# sensor.net
KiCad netlist of a schematic drawn in EAGLE
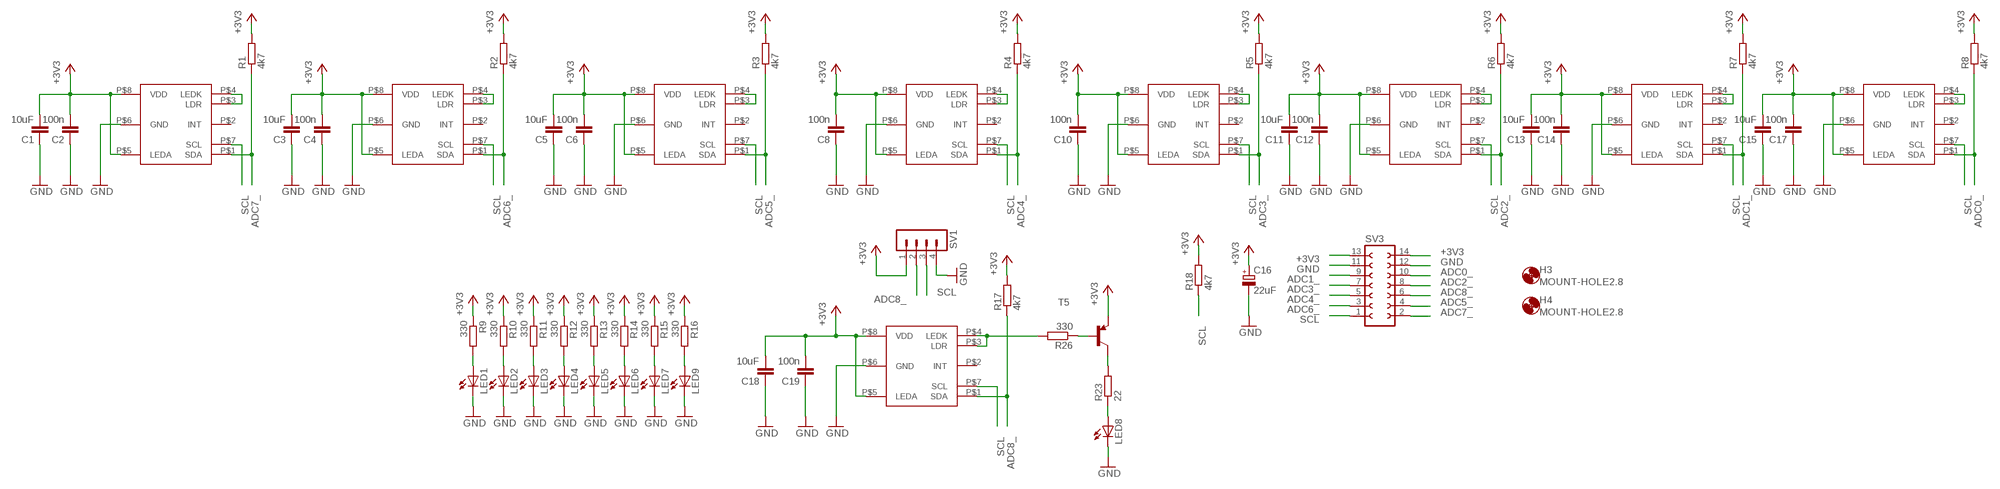
[diagram p0: schematic, sheet 1]

(export (version "E")
  (design (tool "Eeschema 10.0.6"))
  (components
    (comp (ref "C1")
      (value "10uF")
      (footprint "eagle-import:C0805")
      (libsource (lib "eagle-import") (part "C-EUC0805"))
    )
    (comp (ref "C2")
      (value "100n")
      (footprint "eagle-import:C0805")
      (libsource (lib "eagle-import") (part "C-EUC0805"))
    )
    (comp (ref "C3")
      (value "10uF")
      (footprint "eagle-import:C0805")
      (libsource (lib "eagle-import") (part "C-EUC0805"))
    )
    (comp (ref "C4")
      (value "100n")
      (footprint "eagle-import:C0805")
      (libsource (lib "eagle-import") (part "C-EUC0805"))
    )
    (comp (ref "C5")
      (value "10uF")
      (footprint "eagle-import:C0805")
      (libsource (lib "eagle-import") (part "C-EUC0805"))
    )
    (comp (ref "C6")
      (value "100n")
      (footprint "eagle-import:C0805")
      (libsource (lib "eagle-import") (part "C-EUC0805"))
    )
    (comp (ref "C8")
      (value "100n")
      (footprint "eagle-import:C0805")
      (libsource (lib "eagle-import") (part "C-EUC0805"))
    )
    (comp (ref "C10")
      (value "100n")
      (footprint "eagle-import:C0805")
      (libsource (lib "eagle-import") (part "C-EUC0805"))
    )
    (comp (ref "C11")
      (value "10uF")
      (footprint "eagle-import:C0805")
      (libsource (lib "eagle-import") (part "C-EUC0805"))
    )
    (comp (ref "C12")
      (value "100n")
      (footprint "eagle-import:C0805")
      (libsource (lib "eagle-import") (part "C-EUC0805"))
    )
    (comp (ref "C13")
      (value "10uF")
      (footprint "eagle-import:C0805")
      (libsource (lib "eagle-import") (part "C-EUC0805"))
    )
    (comp (ref "C14")
      (value "100n")
      (footprint "eagle-import:C0805")
      (libsource (lib "eagle-import") (part "C-EUC0805"))
    )
    (comp (ref "C15")
      (value "10uF")
      (footprint "eagle-import:C0805")
      (libsource (lib "eagle-import") (part "C-EUC0805"))
    )
    (comp (ref "C16")
      (value "22uF")
      (footprint "eagle-import:153CLV-0505")
      (libsource (lib "eagle-import") (part "CPOL-EU153CLV-0505"))
    )
    (comp (ref "C17")
      (value "100n")
      (footprint "eagle-import:C0805")
      (libsource (lib "eagle-import") (part "C-EUC0805"))
    )
    (comp (ref "C18")
      (value "10uF")
      (footprint "eagle-import:C0805")
      (libsource (lib "eagle-import") (part "C-EUC0805"))
    )
    (comp (ref "C19")
      (value "100n")
      (footprint "eagle-import:C0805")
      (libsource (lib "eagle-import") (part "C-EUC0805"))
    )
    (comp (ref "H3")
      (value "MOUNT-HOLE2.8")
      (footprint "eagle-import:2,8")
      (libsource (lib "eagle-import") (part "MOUNT-HOLE2.8"))
    )
    (comp (ref "H4")
      (value "MOUNT-HOLE2.8")
      (footprint "eagle-import:2,8")
      (libsource (lib "eagle-import") (part "MOUNT-HOLE2.8"))
    )
    (comp (ref "LED1")
      (value "LEDCHIPLED_1206")
      (footprint "eagle-import:CHIPLED_1206")
      (libsource (lib "eagle-import") (part "my_parts_LEDCHIPLED_1206"))
    )
    (comp (ref "LED2")
      (value "LEDCHIPLED_1206")
      (footprint "eagle-import:CHIPLED_1206")
      (libsource (lib "eagle-import") (part "my_parts_LEDCHIPLED_1206"))
    )
    (comp (ref "LED3")
      (value "LEDCHIPLED_1206")
      (footprint "eagle-import:CHIPLED_1206")
      (libsource (lib "eagle-import") (part "my_parts_LEDCHIPLED_1206"))
    )
    (comp (ref "LED4")
      (value "LEDCHIPLED_1206")
      (footprint "eagle-import:CHIPLED_1206")
      (libsource (lib "eagle-import") (part "my_parts_LEDCHIPLED_1206"))
    )
    (comp (ref "LED5")
      (value "LEDCHIPLED_1206")
      (footprint "eagle-import:CHIPLED_1206")
      (libsource (lib "eagle-import") (part "my_parts_LEDCHIPLED_1206"))
    )
    (comp (ref "LED6")
      (value "LEDCHIPLED_1206")
      (footprint "eagle-import:CHIPLED_1206")
      (libsource (lib "eagle-import") (part "my_parts_LEDCHIPLED_1206"))
    )
    (comp (ref "LED7")
      (value "LEDCHIPLED_1206")
      (footprint "eagle-import:CHIPLED_1206")
      (libsource (lib "eagle-import") (part "my_parts_LEDCHIPLED_1206"))
    )
    (comp (ref "LED8")
      (value "LED5MM")
      (footprint "eagle-import:LED5MM")
      (libsource (lib "eagle-import") (part "LED5MM"))
    )
    (comp (ref "LED9")
      (value "LEDCHIPLED_1206")
      (footprint "eagle-import:CHIPLED_1206")
      (libsource (lib "eagle-import") (part "my_parts_LEDCHIPLED_1206"))
    )
    (comp (ref "R1")
      (value "4k7")
      (footprint "eagle-import:M0805")
      (libsource (lib "eagle-import") (part "R-EU_M0805"))
    )
    (comp (ref "R2")
      (value "4k7")
      (footprint "eagle-import:M0805")
      (libsource (lib "eagle-import") (part "R-EU_M0805"))
    )
    (comp (ref "R3")
      (value "4k7")
      (footprint "eagle-import:M0805")
      (libsource (lib "eagle-import") (part "R-EU_M0805"))
    )
    (comp (ref "R4")
      (value "4k7")
      (footprint "eagle-import:M0805")
      (libsource (lib "eagle-import") (part "R-EU_M0805"))
    )
    (comp (ref "R5")
      (value "4k7")
      (footprint "eagle-import:M0805")
      (libsource (lib "eagle-import") (part "R-EU_M0805"))
    )
    (comp (ref "R6")
      (value "4k7")
      (footprint "eagle-import:M0805")
      (libsource (lib "eagle-import") (part "R-EU_M0805"))
    )
    (comp (ref "R7")
      (value "4k7")
      (footprint "eagle-import:M0805")
      (libsource (lib "eagle-import") (part "R-EU_M0805"))
    )
    (comp (ref "R8")
      (value "4k7")
      (footprint "eagle-import:M0805")
      (libsource (lib "eagle-import") (part "R-EU_M0805"))
    )
    (comp (ref "R9")
      (value "330")
      (footprint "eagle-import:M0805")
      (libsource (lib "eagle-import") (part "R-EU_M0805"))
    )
    (comp (ref "R10")
      (value "330")
      (footprint "eagle-import:M0805")
      (libsource (lib "eagle-import") (part "R-EU_M0805"))
    )
    (comp (ref "R11")
      (value "330")
      (footprint "eagle-import:M0805")
      (libsource (lib "eagle-import") (part "R-EU_M0805"))
    )
    (comp (ref "R12")
      (value "330")
      (footprint "eagle-import:M0805")
      (libsource (lib "eagle-import") (part "R-EU_M0805"))
    )
    (comp (ref "R13")
      (value "330")
      (footprint "eagle-import:M0805")
      (libsource (lib "eagle-import") (part "R-EU_M0805"))
    )
    (comp (ref "R14")
      (value "330")
      (footprint "eagle-import:M0805")
      (libsource (lib "eagle-import") (part "R-EU_M0805"))
    )
    (comp (ref "R15")
      (value "330")
      (footprint "eagle-import:M0805")
      (libsource (lib "eagle-import") (part "R-EU_M0805"))
    )
    (comp (ref "R16")
      (value "330")
      (footprint "eagle-import:M0805")
      (libsource (lib "eagle-import") (part "R-EU_M0805"))
    )
    (comp (ref "R17")
      (value "4k7")
      (footprint "eagle-import:M0805")
      (libsource (lib "eagle-import") (part "R-EU_M0805"))
    )
    (comp (ref "R18")
      (value "4k7")
      (footprint "eagle-import:M0805")
      (libsource (lib "eagle-import") (part "R-EU_M0805"))
    )
    (comp (ref "R23")
      (value "22")
      (footprint "eagle-import:M0805")
      (libsource (lib "eagle-import") (part "R-EU_M0805"))
    )
    (comp (ref "R26")
      (value "330")
      (footprint "eagle-import:M0805")
      (libsource (lib "eagle-import") (part "R-EU_M0805"))
    )
    (comp (ref "SV1")
      (value "MA04-1")
      (footprint "eagle-import:MA04-1")
      (libsource (lib "eagle-import") (part "MA04-1"))
    )
    (comp (ref "SV3")
      (value "FE07-2")
      (footprint "eagle-import:FE07-2")
      (libsource (lib "eagle-import") (part "FE07-2"))
    )
    (comp (ref "T5")
      (value "BC857A-PNP-SOT23-BEC")
      (footprint "eagle-import:SOT23-BEC")
      (libsource (lib "eagle-import") (part "-PNP-SOT23-BECBC857A"))
    )
    (comp (ref "U$1")
      (value "APDS9950")
      (footprint "eagle-import:APDS9950")
      (libsource (lib "eagle-import") (part "APDS9950"))
    )
    (comp (ref "U$2")
      (value "APDS9950_EDGE")
      (footprint "eagle-import:APDS9950_EDGE")
      (libsource (lib "eagle-import") (part "APDS9950_EDGE"))
    )
    (comp (ref "U$4")
      (value "APDS9950")
      (footprint "eagle-import:APDS9950")
      (libsource (lib "eagle-import") (part "APDS9950"))
    )
    (comp (ref "U$5")
      (value "APDS9950")
      (footprint "eagle-import:APDS9950")
      (libsource (lib "eagle-import") (part "APDS9950"))
    )
    (comp (ref "U$6")
      (value "APDS9950")
      (footprint "eagle-import:APDS9950")
      (libsource (lib "eagle-import") (part "APDS9950"))
    )
    (comp (ref "U$7")
      (value "APDS9950")
      (footprint "eagle-import:APDS9950")
      (libsource (lib "eagle-import") (part "APDS9950"))
    )
    (comp (ref "U$8")
      (value "APDS9950")
      (footprint "eagle-import:APDS9950")
      (libsource (lib "eagle-import") (part "APDS9950"))
    )
    (comp (ref "U$9")
      (value "APDS9950")
      (footprint "eagle-import:APDS9950")
      (libsource (lib "eagle-import") (part "APDS9950"))
    )
    (comp (ref "U$10")
      (value "APDS9950")
      (footprint "eagle-import:APDS9950")
      (libsource (lib "eagle-import") (part "APDS9950"))
    )
  )
  (nets
    (net (code "1") (name "+3V3") (class "Default")
      (node (ref "C1") (pin "2") (pinfunction "2_2") (pintype "passive"))
      (node (ref "C10") (pin "2") (pinfunction "2_2") (pintype "passive"))
      (node (ref "C11") (pin "2") (pinfunction "2_2") (pintype "passive"))
      (node (ref "C12") (pin "2") (pinfunction "2_2") (pintype "passive"))
      (node (ref "C13") (pin "2") (pinfunction "2_2") (pintype "passive"))
      (node (ref "C14") (pin "2") (pinfunction "2_2") (pintype "passive"))
      (node (ref "C15") (pin "2") (pinfunction "2_2") (pintype "passive"))
      (node (ref "C16") (pin "+") (pinfunction "+_+") (pintype "passive"))
      (node (ref "C17") (pin "2") (pinfunction "2_2") (pintype "passive"))
      (node (ref "C18") (pin "2") (pinfunction "2_2") (pintype "passive"))
      (node (ref "C19") (pin "2") (pinfunction "2_2") (pintype "passive"))
      (node (ref "C2") (pin "2") (pinfunction "2_2") (pintype "passive"))
      (node (ref "C3") (pin "2") (pinfunction "2_2") (pintype "passive"))
      (node (ref "C4") (pin "2") (pinfunction "2_2") (pintype "passive"))
      (node (ref "C5") (pin "2") (pinfunction "2_2") (pintype "passive"))
      (node (ref "C6") (pin "2") (pinfunction "2_2") (pintype "passive"))
      (node (ref "C8") (pin "2") (pinfunction "2_2") (pintype "passive"))
      (node (ref "R1") (pin "2") (pinfunction "2_2") (pintype "passive"))
      (node (ref "R10") (pin "1") (pinfunction "1_1") (pintype "passive"))
      (node (ref "R11") (pin "1") (pinfunction "1_1") (pintype "passive"))
      (node (ref "R12") (pin "1") (pinfunction "1_1") (pintype "passive"))
      (node (ref "R13") (pin "1") (pinfunction "1_1") (pintype "passive"))
      (node (ref "R14") (pin "1") (pinfunction "1_1") (pintype "passive"))
      (node (ref "R15") (pin "1") (pinfunction "1_1") (pintype "passive"))
      (node (ref "R16") (pin "1") (pinfunction "1_1") (pintype "passive"))
      (node (ref "R17") (pin "2") (pinfunction "2_2") (pintype "passive"))
      (node (ref "R18") (pin "2") (pinfunction "2_2") (pintype "passive"))
      (node (ref "R2") (pin "2") (pinfunction "2_2") (pintype "passive"))
      (node (ref "R3") (pin "2") (pinfunction "2_2") (pintype "passive"))
      (node (ref "R4") (pin "2") (pinfunction "2_2") (pintype "passive"))
      (node (ref "R5") (pin "2") (pinfunction "2_2") (pintype "passive"))
      (node (ref "R6") (pin "2") (pinfunction "2_2") (pintype "passive"))
      (node (ref "R7") (pin "2") (pinfunction "2_2") (pintype "passive"))
      (node (ref "R8") (pin "2") (pinfunction "2_2") (pintype "passive"))
      (node (ref "R9") (pin "1") (pinfunction "1_1") (pintype "passive"))
      (node (ref "SV1") (pin "1") (pinfunction "1_1") (pintype "passive"))
      (node (ref "SV3") (pin "13") (pinfunction "13_13") (pintype "passive"))
      (node (ref "SV3") (pin "14") (pinfunction "14_14") (pintype "passive"))
      (node (ref "T5") (pin "E") (pinfunction "E_E") (pintype "passive"))
      (node (ref "U$1") (pin "P$5") (pinfunction "LEDA_P$5") (pintype "bidirectional"))
      (node (ref "U$1") (pin "P$8") (pinfunction "VDD_P$8") (pintype "bidirectional"))
      (node (ref "U$10") (pin "P$5") (pinfunction "LEDA_P$5") (pintype "bidirectional"))
      (node (ref "U$10") (pin "P$8") (pinfunction "VDD_P$8") (pintype "bidirectional"))
      (node (ref "U$2") (pin "P$5") (pinfunction "LEDA_P$5") (pintype "bidirectional"))
      (node (ref "U$2") (pin "P$8") (pinfunction "VDD_P$8") (pintype "bidirectional"))
      (node (ref "U$4") (pin "P$5") (pinfunction "LEDA_P$5") (pintype "bidirectional"))
      (node (ref "U$4") (pin "P$8") (pinfunction "VDD_P$8") (pintype "bidirectional"))
      (node (ref "U$5") (pin "P$5") (pinfunction "LEDA_P$5") (pintype "bidirectional"))
      (node (ref "U$5") (pin "P$8") (pinfunction "VDD_P$8") (pintype "bidirectional"))
      (node (ref "U$6") (pin "P$5") (pinfunction "LEDA_P$5") (pintype "bidirectional"))
      (node (ref "U$6") (pin "P$8") (pinfunction "VDD_P$8") (pintype "bidirectional"))
      (node (ref "U$7") (pin "P$5") (pinfunction "LEDA_P$5") (pintype "bidirectional"))
      (node (ref "U$7") (pin "P$8") (pinfunction "VDD_P$8") (pintype "bidirectional"))
      (node (ref "U$8") (pin "P$5") (pinfunction "LEDA_P$5") (pintype "bidirectional"))
      (node (ref "U$8") (pin "P$8") (pinfunction "VDD_P$8") (pintype "bidirectional"))
      (node (ref "U$9") (pin "P$5") (pinfunction "LEDA_P$5") (pintype "bidirectional"))
      (node (ref "U$9") (pin "P$8") (pinfunction "VDD_P$8") (pintype "bidirectional"))
    )
    (net (code "2") (name "/ADC0_") (class "Default")
      (node (ref "R8") (pin "1") (pinfunction "1_1") (pintype "passive"))
      (node (ref "SV3") (pin "10") (pinfunction "10_10") (pintype "passive"))
      (node (ref "U$10") (pin "P$1") (pinfunction "SDA_P$1") (pintype "bidirectional"))
    )
    (net (code "3") (name "/ADC1_") (class "Default")
      (node (ref "R7") (pin "1") (pinfunction "1_1") (pintype "passive"))
      (node (ref "SV3") (pin "9") (pinfunction "9_9") (pintype "passive"))
      (node (ref "U$9") (pin "P$1") (pinfunction "SDA_P$1") (pintype "bidirectional"))
    )
    (net (code "4") (name "/ADC2_") (class "Default")
      (node (ref "R6") (pin "1") (pinfunction "1_1") (pintype "passive"))
      (node (ref "SV3") (pin "8") (pinfunction "8_8") (pintype "passive"))
      (node (ref "U$8") (pin "P$1") (pinfunction "SDA_P$1") (pintype "bidirectional"))
    )
    (net (code "5") (name "/ADC3_") (class "Default")
      (node (ref "R5") (pin "1") (pinfunction "1_1") (pintype "passive"))
      (node (ref "SV3") (pin "7") (pinfunction "7_7") (pintype "passive"))
      (node (ref "U$7") (pin "P$1") (pinfunction "SDA_P$1") (pintype "bidirectional"))
    )
    (net (code "6") (name "/ADC4_") (class "Default")
      (node (ref "R4") (pin "1") (pinfunction "1_1") (pintype "passive"))
      (node (ref "SV3") (pin "5") (pinfunction "5_5") (pintype "passive"))
      (node (ref "U$6") (pin "P$1") (pinfunction "SDA_P$1") (pintype "bidirectional"))
    )
    (net (code "7") (name "/ADC5_") (class "Default")
      (node (ref "R3") (pin "1") (pinfunction "1_1") (pintype "passive"))
      (node (ref "SV3") (pin "4") (pinfunction "4_4") (pintype "passive"))
      (node (ref "U$5") (pin "P$1") (pinfunction "SDA_P$1") (pintype "bidirectional"))
    )
    (net (code "8") (name "/ADC6_") (class "Default")
      (node (ref "R2") (pin "1") (pinfunction "1_1") (pintype "passive"))
      (node (ref "SV3") (pin "3") (pinfunction "3_3") (pintype "passive"))
      (node (ref "U$4") (pin "P$1") (pinfunction "SDA_P$1") (pintype "bidirectional"))
    )
    (net (code "9") (name "/ADC7_") (class "Default")
      (node (ref "R1") (pin "1") (pinfunction "1_1") (pintype "passive"))
      (node (ref "SV3") (pin "2") (pinfunction "2_2") (pintype "passive"))
      (node (ref "U$1") (pin "P$1") (pinfunction "SDA_P$1") (pintype "bidirectional"))
    )
    (net (code "10") (name "/ADC8_") (class "Default")
      (node (ref "R17") (pin "1") (pinfunction "1_1") (pintype "passive"))
      (node (ref "SV1") (pin "2") (pinfunction "2_2") (pintype "passive"))
      (node (ref "SV3") (pin "6") (pinfunction "6_6") (pintype "passive"))
      (node (ref "U$2") (pin "P$1") (pinfunction "SDA_P$1") (pintype "bidirectional"))
    )
    (net (code "11") (name "/SCL") (class "Default")
      (node (ref "R18") (pin "1") (pinfunction "1_1") (pintype "passive"))
      (node (ref "SV1") (pin "3") (pinfunction "3_3") (pintype "passive"))
      (node (ref "SV3") (pin "1") (pinfunction "1_1") (pintype "passive"))
      (node (ref "U$1") (pin "P$7") (pinfunction "SCL_P$7") (pintype "bidirectional"))
      (node (ref "U$10") (pin "P$7") (pinfunction "SCL_P$7") (pintype "bidirectional"))
      (node (ref "U$2") (pin "P$7") (pinfunction "SCL_P$7") (pintype "bidirectional"))
      (node (ref "U$4") (pin "P$7") (pinfunction "SCL_P$7") (pintype "bidirectional"))
      (node (ref "U$5") (pin "P$7") (pinfunction "SCL_P$7") (pintype "bidirectional"))
      (node (ref "U$6") (pin "P$7") (pinfunction "SCL_P$7") (pintype "bidirectional"))
      (node (ref "U$7") (pin "P$7") (pinfunction "SCL_P$7") (pintype "bidirectional"))
      (node (ref "U$8") (pin "P$7") (pinfunction "SCL_P$7") (pintype "bidirectional"))
      (node (ref "U$9") (pin "P$7") (pinfunction "SCL_P$7") (pintype "bidirectional"))
    )
    (net (code "12") (name "GND") (class "Default")
      (node (ref "C1") (pin "1") (pinfunction "1_1") (pintype "passive"))
      (node (ref "C10") (pin "1") (pinfunction "1_1") (pintype "passive"))
      (node (ref "C11") (pin "1") (pinfunction "1_1") (pintype "passive"))
      (node (ref "C12") (pin "1") (pinfunction "1_1") (pintype "passive"))
      (node (ref "C13") (pin "1") (pinfunction "1_1") (pintype "passive"))
      (node (ref "C14") (pin "1") (pinfunction "1_1") (pintype "passive"))
      (node (ref "C15") (pin "1") (pinfunction "1_1") (pintype "passive"))
      (node (ref "C16") (pin "-") (pinfunction "-_-") (pintype "passive"))
      (node (ref "C17") (pin "1") (pinfunction "1_1") (pintype "passive"))
      (node (ref "C18") (pin "1") (pinfunction "1_1") (pintype "passive"))
      (node (ref "C19") (pin "1") (pinfunction "1_1") (pintype "passive"))
      (node (ref "C2") (pin "1") (pinfunction "1_1") (pintype "passive"))
      (node (ref "C3") (pin "1") (pinfunction "1_1") (pintype "passive"))
      (node (ref "C4") (pin "1") (pinfunction "1_1") (pintype "passive"))
      (node (ref "C5") (pin "1") (pinfunction "1_1") (pintype "passive"))
      (node (ref "C6") (pin "1") (pinfunction "1_1") (pintype "passive"))
      (node (ref "C8") (pin "1") (pinfunction "1_1") (pintype "passive"))
      (node (ref "LED1") (pin "C") (pinfunction "C_C") (pintype "passive"))
      (node (ref "LED2") (pin "C") (pinfunction "C_C") (pintype "passive"))
      (node (ref "LED3") (pin "C") (pinfunction "C_C") (pintype "passive"))
      (node (ref "LED4") (pin "C") (pinfunction "C_C") (pintype "passive"))
      (node (ref "LED5") (pin "C") (pinfunction "C_C") (pintype "passive"))
      (node (ref "LED6") (pin "C") (pinfunction "C_C") (pintype "passive"))
      (node (ref "LED7") (pin "C") (pinfunction "C_C") (pintype "passive"))
      (node (ref "LED8") (pin "K") (pinfunction "C_K") (pintype "passive"))
      (node (ref "LED9") (pin "C") (pinfunction "C_C") (pintype "passive"))
      (node (ref "SV1") (pin "4") (pinfunction "4_4") (pintype "passive"))
      (node (ref "SV3") (pin "11") (pinfunction "11_11") (pintype "passive"))
      (node (ref "SV3") (pin "12") (pinfunction "12_12") (pintype "passive"))
      (node (ref "U$1") (pin "P$6") (pinfunction "GND_P$6") (pintype "bidirectional"))
      (node (ref "U$10") (pin "P$6") (pinfunction "GND_P$6") (pintype "bidirectional"))
      (node (ref "U$2") (pin "P$6") (pinfunction "GND_P$6") (pintype "bidirectional"))
      (node (ref "U$4") (pin "P$6") (pinfunction "GND_P$6") (pintype "bidirectional"))
      (node (ref "U$5") (pin "P$6") (pinfunction "GND_P$6") (pintype "bidirectional"))
      (node (ref "U$6") (pin "P$6") (pinfunction "GND_P$6") (pintype "bidirectional"))
      (node (ref "U$7") (pin "P$6") (pinfunction "GND_P$6") (pintype "bidirectional"))
      (node (ref "U$8") (pin "P$6") (pinfunction "GND_P$6") (pintype "bidirectional"))
      (node (ref "U$9") (pin "P$6") (pinfunction "GND_P$6") (pintype "bidirectional"))
    )
    (net (code "13") (name "Net-(LED1-PadA)") (class "Default")
      (node (ref "LED1") (pin "A") (pinfunction "A_A") (pintype "passive"))
      (node (ref "R9") (pin "2") (pinfunction "2_2") (pintype "passive"))
    )
    (net (code "14") (name "Net-(LED2-PadA)") (class "Default")
      (node (ref "LED2") (pin "A") (pinfunction "A_A") (pintype "passive"))
      (node (ref "R10") (pin "2") (pinfunction "2_2") (pintype "passive"))
    )
    (net (code "15") (name "Net-(LED3-PadA)") (class "Default")
      (node (ref "LED3") (pin "A") (pinfunction "A_A") (pintype "passive"))
      (node (ref "R11") (pin "2") (pinfunction "2_2") (pintype "passive"))
    )
    (net (code "16") (name "Net-(LED4-PadA)") (class "Default")
      (node (ref "LED4") (pin "A") (pinfunction "A_A") (pintype "passive"))
      (node (ref "R12") (pin "2") (pinfunction "2_2") (pintype "passive"))
    )
    (net (code "17") (name "Net-(LED5-PadA)") (class "Default")
      (node (ref "LED5") (pin "A") (pinfunction "A_A") (pintype "passive"))
      (node (ref "R13") (pin "2") (pinfunction "2_2") (pintype "passive"))
    )
    (net (code "18") (name "Net-(LED6-PadA)") (class "Default")
      (node (ref "LED6") (pin "A") (pinfunction "A_A") (pintype "passive"))
      (node (ref "R14") (pin "2") (pinfunction "2_2") (pintype "passive"))
    )
    (net (code "19") (name "Net-(LED7-PadA)") (class "Default")
      (node (ref "LED7") (pin "A") (pinfunction "A_A") (pintype "passive"))
      (node (ref "R15") (pin "2") (pinfunction "2_2") (pintype "passive"))
    )
    (net (code "20") (name "Net-(LED8-PadA)") (class "Default")
      (node (ref "LED8") (pin "A") (pinfunction "A_A") (pintype "passive"))
      (node (ref "R23") (pin "1") (pinfunction "1_1") (pintype "passive"))
    )
    (net (code "21") (name "Net-(LED9-PadA)") (class "Default")
      (node (ref "LED9") (pin "A") (pinfunction "A_A") (pintype "passive"))
      (node (ref "R16") (pin "2") (pinfunction "2_2") (pintype "passive"))
    )
    (net (code "22") (name "Net-(R23-Pad2)") (class "Default")
      (node (ref "R23") (pin "2") (pinfunction "2_2") (pintype "passive"))
      (node (ref "T5") (pin "C") (pinfunction "C_C") (pintype "passive"))
    )
    (net (code "23") (name "Net-(R26-Pad1)") (class "Default")
      (node (ref "R26") (pin "1") (pinfunction "1_1") (pintype "passive"))
      (node (ref "T5") (pin "B") (pinfunction "B_B") (pintype "passive"))
    )
    (net (code "24") (name "Net-(U$1-LDR)") (class "Default")
      (node (ref "U$1") (pin "P$3") (pinfunction "LDR_P$3") (pintype "bidirectional"))
      (node (ref "U$1") (pin "P$4") (pinfunction "LEDK_P$4") (pintype "bidirectional"))
    )
    (net (code "25") (name "Net-(U$2-LDR)") (class "Default")
      (node (ref "R26") (pin "2") (pinfunction "2_2") (pintype "passive"))
      (node (ref "U$2") (pin "P$3") (pinfunction "LDR_P$3") (pintype "bidirectional"))
      (node (ref "U$2") (pin "P$4") (pinfunction "LEDK_P$4") (pintype "bidirectional"))
    )
    (net (code "26") (name "Net-(U$4-LDR)") (class "Default")
      (node (ref "U$4") (pin "P$3") (pinfunction "LDR_P$3") (pintype "bidirectional"))
      (node (ref "U$4") (pin "P$4") (pinfunction "LEDK_P$4") (pintype "bidirectional"))
    )
    (net (code "27") (name "Net-(U$5-LDR)") (class "Default")
      (node (ref "U$5") (pin "P$3") (pinfunction "LDR_P$3") (pintype "bidirectional"))
      (node (ref "U$5") (pin "P$4") (pinfunction "LEDK_P$4") (pintype "bidirectional"))
    )
    (net (code "28") (name "Net-(U$6-LDR)") (class "Default")
      (node (ref "U$6") (pin "P$3") (pinfunction "LDR_P$3") (pintype "bidirectional"))
      (node (ref "U$6") (pin "P$4") (pinfunction "LEDK_P$4") (pintype "bidirectional"))
    )
    (net (code "29") (name "Net-(U$7-LDR)") (class "Default")
      (node (ref "U$7") (pin "P$3") (pinfunction "LDR_P$3") (pintype "bidirectional"))
      (node (ref "U$7") (pin "P$4") (pinfunction "LEDK_P$4") (pintype "bidirectional"))
    )
    (net (code "30") (name "Net-(U$8-LDR)") (class "Default")
      (node (ref "U$8") (pin "P$3") (pinfunction "LDR_P$3") (pintype "bidirectional"))
      (node (ref "U$8") (pin "P$4") (pinfunction "LEDK_P$4") (pintype "bidirectional"))
    )
    (net (code "31") (name "Net-(U$9-LDR)") (class "Default")
      (node (ref "U$9") (pin "P$3") (pinfunction "LDR_P$3") (pintype "bidirectional"))
      (node (ref "U$9") (pin "P$4") (pinfunction "LEDK_P$4") (pintype "bidirectional"))
    )
    (net (code "32") (name "Net-(U$10-LDR)") (class "Default")
      (node (ref "U$10") (pin "P$3") (pinfunction "LDR_P$3") (pintype "bidirectional"))
      (node (ref "U$10") (pin "P$4") (pinfunction "LEDK_P$4") (pintype "bidirectional"))
    )
    (net (code "33") (name "unconnected-(U$1-INT-PadP$2)") (class "Default")
      (node (ref "U$1") (pin "P$2") (pinfunction "INT_P$2") (pintype "bidirectional"))
    )
    (net (code "34") (name "unconnected-(U$2-INT-PadP$2)") (class "Default")
      (node (ref "U$2") (pin "P$2") (pinfunction "INT_P$2") (pintype "bidirectional"))
    )
    (net (code "35") (name "unconnected-(U$4-INT-PadP$2)") (class "Default")
      (node (ref "U$4") (pin "P$2") (pinfunction "INT_P$2") (pintype "bidirectional"))
    )
    (net (code "36") (name "unconnected-(U$5-INT-PadP$2)") (class "Default")
      (node (ref "U$5") (pin "P$2") (pinfunction "INT_P$2") (pintype "bidirectional"))
    )
    (net (code "37") (name "unconnected-(U$6-INT-PadP$2)") (class "Default")
      (node (ref "U$6") (pin "P$2") (pinfunction "INT_P$2") (pintype "bidirectional"))
    )
    (net (code "38") (name "unconnected-(U$7-INT-PadP$2)") (class "Default")
      (node (ref "U$7") (pin "P$2") (pinfunction "INT_P$2") (pintype "bidirectional"))
    )
    (net (code "39") (name "unconnected-(U$8-INT-PadP$2)") (class "Default")
      (node (ref "U$8") (pin "P$2") (pinfunction "INT_P$2") (pintype "bidirectional"))
    )
    (net (code "40") (name "unconnected-(U$9-INT-PadP$2)") (class "Default")
      (node (ref "U$9") (pin "P$2") (pinfunction "INT_P$2") (pintype "bidirectional"))
    )
    (net (code "41") (name "unconnected-(U$10-INT-PadP$2)") (class "Default")
      (node (ref "U$10") (pin "P$2") (pinfunction "INT_P$2") (pintype "bidirectional"))
    )
  )
)
